# shield-imu.net
KiCad netlist of a schematic drawn in EAGLE
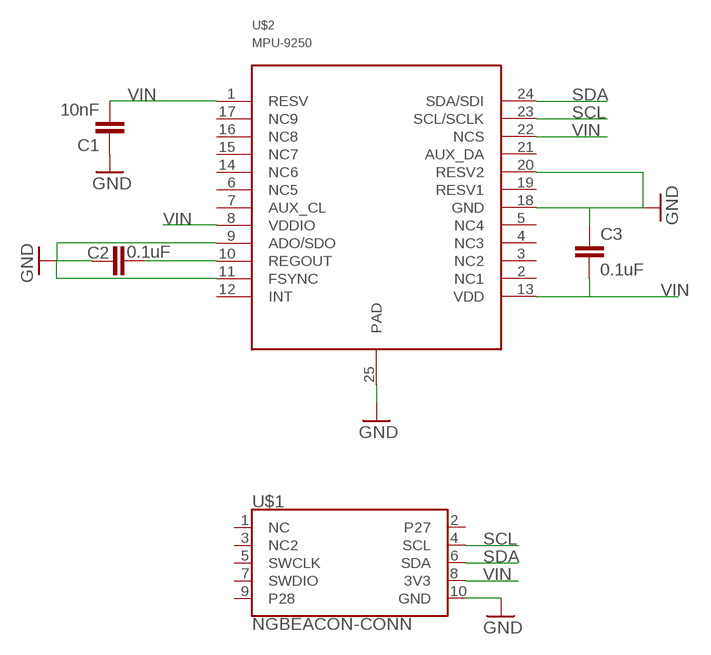
[diagram p0: schematic, sheet 1]

(export (version "E")
  (design (tool "Eeschema 10.0.6"))
  (components
    (comp (ref "C1")
      (value "10nF")
      (footprint "eagle-import:0603-CAP")
      (libsource (lib "eagle-import") (part "10NF/10000PF-50V-10%(0603)"))
    )
    (comp (ref "C2")
      (value "0.1uF")
      (footprint "eagle-import:0603-CAP")
      (libsource (lib "eagle-import") (part "0.1UF-25V-5%(0603)"))
    )
    (comp (ref "C3")
      (value "0.1uF")
      (footprint "eagle-import:0603-CAP")
      (libsource (lib "eagle-import") (part "0.1UF-25V-5%(0603)"))
    )
    (comp (ref "U$1")
      (value "NGBEACON-CONN")
      (footprint "eagle-import:2X5-PTH-1.27MM")
      (libsource (lib "eagle-import") (part "NGBEACON-CONN"))
    )
    (comp (ref "U$2")
      (value "MPU-9250")
      (footprint "eagle-import:LEAD-QFN24")
      (libsource (lib "eagle-import") (part "MPU-9250"))
    )
  )
  (nets
    (net (code "1") (name "/SCL") (class "Default")
      (node (ref "U$1") (pin "4") (pinfunction "SCL_4") (pintype "bidirectional"))
      (node (ref "U$2") (pin "23") (pinfunction "SCL/SCLK_23") (pintype "bidirectional"))
    )
    (net (code "2") (name "/SDA") (class "Default")
      (node (ref "U$1") (pin "6") (pinfunction "SDA_6") (pintype "bidirectional"))
      (node (ref "U$2") (pin "24") (pinfunction "SDA/SDI_24") (pintype "bidirectional"))
    )
    (net (code "3") (name "/VIN") (class "Default")
      (node (ref "C1") (pin "2") (pinfunction "2_2") (pintype "passive"))
      (node (ref "C3") (pin "2") (pinfunction "2_2") (pintype "passive"))
      (node (ref "U$1") (pin "8") (pinfunction "3V3_8") (pintype "bidirectional"))
      (node (ref "U$2") (pin "1") (pinfunction "RESV_1") (pintype "bidirectional"))
      (node (ref "U$2") (pin "13") (pinfunction "VDD_13") (pintype "bidirectional"))
      (node (ref "U$2") (pin "22") (pinfunction "NCS_22") (pintype "bidirectional"))
      (node (ref "U$2") (pin "8") (pinfunction "VDDIO_8") (pintype "bidirectional"))
    )
    (net (code "4") (name "GND") (class "Default")
      (node (ref "C1") (pin "1") (pinfunction "1_1") (pintype "passive"))
      (node (ref "C2") (pin "1") (pinfunction "1_1") (pintype "passive"))
      (node (ref "C3") (pin "1") (pinfunction "1_1") (pintype "passive"))
      (node (ref "U$1") (pin "10") (pinfunction "GND_10") (pintype "bidirectional"))
      (node (ref "U$2") (pin "11") (pinfunction "FSYNC_11") (pintype "bidirectional"))
      (node (ref "U$2") (pin "18") (pinfunction "GND_18") (pintype "bidirectional"))
      (node (ref "U$2") (pin "20") (pinfunction "RESV2_20") (pintype "bidirectional"))
      (node (ref "U$2") (pin "25") (pinfunction "PAD_25") (pintype "bidirectional"))
      (node (ref "U$2") (pin "9") (pinfunction "ADO/SDO_9") (pintype "bidirectional"))
    )
    (net (code "5") (name "Net-(U$2-REGOUT)") (class "Default")
      (node (ref "C2") (pin "2") (pinfunction "2_2") (pintype "passive"))
      (node (ref "U$2") (pin "10") (pinfunction "REGOUT_10") (pintype "bidirectional"))
    )
    (net (code "6") (name "unconnected-(U$1-NC-Pad1)") (class "Default")
      (node (ref "U$1") (pin "1") (pinfunction "NC_1") (pintype "bidirectional"))
    )
    (net (code "7") (name "unconnected-(U$1-NC2-Pad3)") (class "Default")
      (node (ref "U$1") (pin "3") (pinfunction "NC2_3") (pintype "bidirectional"))
    )
    (net (code "8") (name "unconnected-(U$1-P27-Pad2)") (class "Default")
      (node (ref "U$1") (pin "2") (pinfunction "P27_2") (pintype "bidirectional"))
    )
    (net (code "9") (name "unconnected-(U$1-P28-Pad9)") (class "Default")
      (node (ref "U$1") (pin "9") (pinfunction "P28_9") (pintype "bidirectional"))
    )
    (net (code "10") (name "unconnected-(U$1-SWCLK-Pad5)") (class "Default")
      (node (ref "U$1") (pin "5") (pinfunction "SWCLK_5") (pintype "bidirectional"))
    )
    (net (code "11") (name "unconnected-(U$1-SWDIO-Pad7)") (class "Default")
      (node (ref "U$1") (pin "7") (pinfunction "SWDIO_7") (pintype "bidirectional"))
    )
    (net (code "12") (name "unconnected-(U$2-AUX_CL-Pad7)") (class "Default")
      (node (ref "U$2") (pin "7") (pinfunction "AUX_CL_7") (pintype "bidirectional"))
    )
    (net (code "13") (name "unconnected-(U$2-AUX_DA-Pad21)") (class "Default")
      (node (ref "U$2") (pin "21") (pinfunction "AUX_DA_21") (pintype "bidirectional"))
    )
    (net (code "14") (name "unconnected-(U$2-INT-Pad12)") (class "Default")
      (node (ref "U$2") (pin "12") (pinfunction "INT_12") (pintype "bidirectional"))
    )
    (net (code "15") (name "unconnected-(U$2-NC1-Pad2)") (class "Default")
      (node (ref "U$2") (pin "2") (pinfunction "NC1_2") (pintype "bidirectional"))
    )
    (net (code "16") (name "unconnected-(U$2-NC2-Pad3)") (class "Default")
      (node (ref "U$2") (pin "3") (pinfunction "NC2_3") (pintype "bidirectional"))
    )
    (net (code "17") (name "unconnected-(U$2-NC3-Pad4)") (class "Default")
      (node (ref "U$2") (pin "4") (pinfunction "NC3_4") (pintype "bidirectional"))
    )
    (net (code "18") (name "unconnected-(U$2-NC4-Pad5)") (class "Default")
      (node (ref "U$2") (pin "5") (pinfunction "NC4_5") (pintype "bidirectional"))
    )
    (net (code "19") (name "unconnected-(U$2-NC5-Pad6)") (class "Default")
      (node (ref "U$2") (pin "6") (pinfunction "NC5_6") (pintype "bidirectional"))
    )
    (net (code "20") (name "unconnected-(U$2-NC6-Pad14)") (class "Default")
      (node (ref "U$2") (pin "14") (pinfunction "NC6_14") (pintype "bidirectional"))
    )
    (net (code "21") (name "unconnected-(U$2-NC7-Pad15)") (class "Default")
      (node (ref "U$2") (pin "15") (pinfunction "NC7_15") (pintype "bidirectional"))
    )
    (net (code "22") (name "unconnected-(U$2-NC8-Pad16)") (class "Default")
      (node (ref "U$2") (pin "16") (pinfunction "NC8_16") (pintype "bidirectional"))
    )
    (net (code "23") (name "unconnected-(U$2-NC9-Pad17)") (class "Default")
      (node (ref "U$2") (pin "17") (pinfunction "NC9_17") (pintype "bidirectional"))
    )
    (net (code "24") (name "unconnected-(U$2-RESV1-Pad19)") (class "Default")
      (node (ref "U$2") (pin "19") (pinfunction "RESV1_19") (pintype "bidirectional"))
    )
  )
)
